# USB_Sound_Card_with_PCM2902.net
KiCad netlist of a schematic drawn in EAGLE
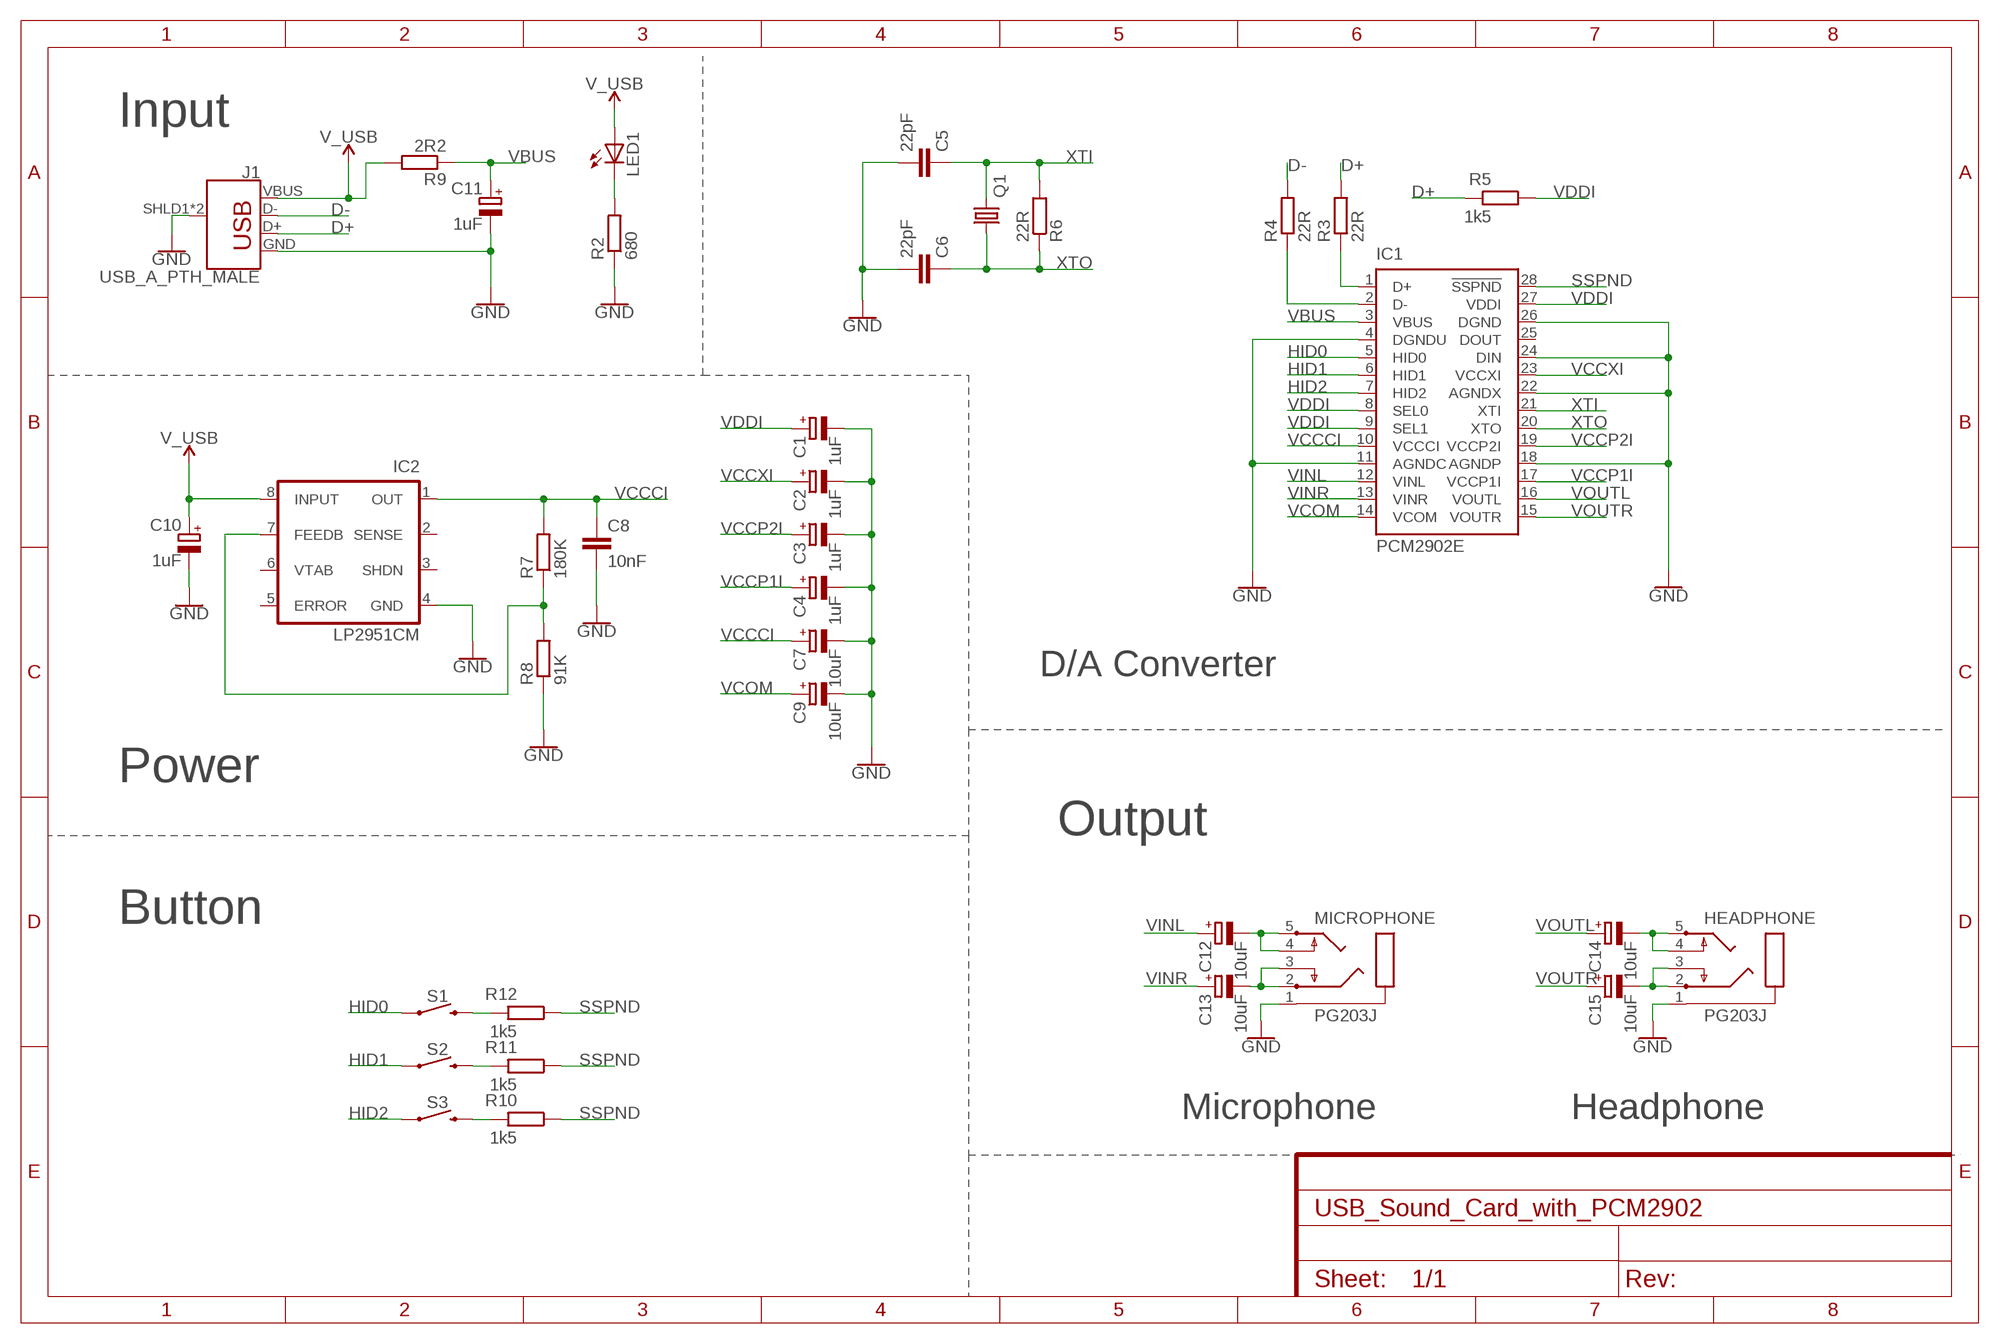
[diagram p0: schematic, sheet 1]

(export (version "E")
  (design (tool "Eeschema 10.0.6"))
  (components
    (comp (ref "C1")
      (value "1uF")
      (footprint "eagle-import:CT3528")
      (libsource (lib "eagle-import") (part "CPOL-EUCT3528"))
    )
    (comp (ref "C2")
      (value "1uF")
      (footprint "eagle-import:CT3528")
      (libsource (lib "eagle-import") (part "CPOL-EUCT3528"))
    )
    (comp (ref "C3")
      (value "1uF")
      (footprint "eagle-import:CT3528")
      (libsource (lib "eagle-import") (part "CPOL-EUCT3528"))
    )
    (comp (ref "C4")
      (value "1uF")
      (footprint "eagle-import:CT3528")
      (libsource (lib "eagle-import") (part "CPOL-EUCT3528"))
    )
    (comp (ref "C5")
      (value "22pF")
      (footprint "eagle-import:C0805")
      (libsource (lib "eagle-import") (part "C-EUC0805"))
    )
    (comp (ref "C6")
      (value "22pF")
      (footprint "eagle-import:C0805")
      (libsource (lib "eagle-import") (part "C-EUC0805"))
    )
    (comp (ref "C7")
      (value "10uF")
      (footprint "eagle-import:CT3528")
      (libsource (lib "eagle-import") (part "CPOL-EUCT3528"))
    )
    (comp (ref "C8")
      (value "10nF")
      (footprint "eagle-import:C0805")
      (libsource (lib "eagle-import") (part "C-EUC0805"))
    )
    (comp (ref "C9")
      (value "10uF")
      (footprint "eagle-import:CT3528")
      (libsource (lib "eagle-import") (part "CPOL-EUCT3528"))
    )
    (comp (ref "C10")
      (value "1uF")
      (footprint "eagle-import:CT3528")
      (libsource (lib "eagle-import") (part "CPOL-EUCT3528"))
    )
    (comp (ref "C11")
      (value "1uF")
      (footprint "eagle-import:CT3528")
      (libsource (lib "eagle-import") (part "CPOL-EUCT3528"))
    )
    (comp (ref "C12")
      (value "10uF")
      (footprint "eagle-import:CT3528")
      (libsource (lib "eagle-import") (part "CPOL-EUCT3528"))
    )
    (comp (ref "C13")
      (value "10uF")
      (footprint "eagle-import:CT3528")
      (libsource (lib "eagle-import") (part "CPOL-EUCT3528"))
    )
    (comp (ref "C14")
      (value "10uF")
      (footprint "eagle-import:CT3528")
      (libsource (lib "eagle-import") (part "CPOL-EUCT3528"))
    )
    (comp (ref "C15")
      (value "10uF")
      (footprint "eagle-import:CT3528")
      (libsource (lib "eagle-import") (part "CPOL-EUCT3528"))
    )
    (comp (ref "HEADPHONE")
      (value "PG203J")
      (footprint "eagle-import:PG203J")
      (libsource (lib "eagle-import") (part "PG203J"))
    )
    (comp (ref "IC1")
      (value "PCM2902E")
      (footprint "eagle-import:SSOP28DB")
      (libsource (lib "eagle-import") (part "PCM2902E"))
    )
    (comp (ref "IC2")
      (value "LP2951CM")
      (footprint "eagle-import:SO-08")
      (libsource (lib "eagle-import") (part "LP2951?CM"))
    )
    (comp (ref "J1")
      (value "USB_A_PTH_MALE")
      (footprint "eagle-import:USB-A-H")
      (libsource (lib "eagle-import") (part "USB_A_PTH_MALE"))
    )
    (comp (ref "LED1")
      (value "LEDCHIP-LED0805")
      (footprint "eagle-import:CHIP-LED0805")
      (libsource (lib "eagle-import") (part "LEDCHIP-LED0805"))
    )
    (comp (ref "MICROPHONE")
      (value "PG203J")
      (footprint "eagle-import:PG203J")
      (libsource (lib "eagle-import") (part "PG203J"))
    )
    (comp (ref "Q1")
      (value "CRYSTALHC49UP")
      (footprint "eagle-import:HC49UP")
      (libsource (lib "eagle-import") (part "CRYSTALHC49UP"))
    )
    (comp (ref "R2")
      (value "680")
      (footprint "eagle-import:M0805")
      (libsource (lib "eagle-import") (part "R-EU_M0805"))
    )
    (comp (ref "R3")
      (value "22R")
      (footprint "eagle-import:M0805")
      (libsource (lib "eagle-import") (part "R-EU_M0805"))
    )
    (comp (ref "R4")
      (value "22R")
      (footprint "eagle-import:M0805")
      (libsource (lib "eagle-import") (part "R-EU_M0805"))
    )
    (comp (ref "R5")
      (value "1k5")
      (footprint "eagle-import:M0805")
      (libsource (lib "eagle-import") (part "R-EU_M0805"))
    )
    (comp (ref "R6")
      (value "22R")
      (footprint "eagle-import:M0805")
      (libsource (lib "eagle-import") (part "R-EU_M0805"))
    )
    (comp (ref "R7")
      (value "180K")
      (footprint "eagle-import:M0805")
      (libsource (lib "eagle-import") (part "R-EU_M0805"))
    )
    (comp (ref "R8")
      (value "91K")
      (footprint "eagle-import:M0805")
      (libsource (lib "eagle-import") (part "R-EU_M0805"))
    )
    (comp (ref "R9")
      (value "2R2")
      (footprint "eagle-import:M0805")
      (libsource (lib "eagle-import") (part "R-EU_M0805"))
    )
    (comp (ref "R10")
      (value "1k5")
      (footprint "eagle-import:M0805")
      (libsource (lib "eagle-import") (part "R-EU_M0805"))
    )
    (comp (ref "R11")
      (value "1k5")
      (footprint "eagle-import:M0805")
      (libsource (lib "eagle-import") (part "R-EU_M0805"))
    )
    (comp (ref "R12")
      (value "1k5")
      (footprint "eagle-import:M0805")
      (libsource (lib "eagle-import") (part "R-EU_M0805"))
    )
    (comp (ref "S1")
      (value "MOMENTARY-SWITCH-SPST-PTH-6.0MM")
      (footprint "eagle-import:TACTILE_SWITCH_PTH_6.0MM")
      (libsource (lib "eagle-import") (part "MOMENTARY-SWITCH-SPST-PTH-6.0MM"))
    )
    (comp (ref "S2")
      (value "MOMENTARY-SWITCH-SPST-PTH-6.0MM")
      (footprint "eagle-import:TACTILE_SWITCH_PTH_6.0MM")
      (libsource (lib "eagle-import") (part "MOMENTARY-SWITCH-SPST-PTH-6.0MM"))
    )
    (comp (ref "S3")
      (value "MOMENTARY-SWITCH-SPST-PTH-6.0MM")
      (footprint "eagle-import:TACTILE_SWITCH_PTH_6.0MM")
      (libsource (lib "eagle-import") (part "MOMENTARY-SWITCH-SPST-PTH-6.0MM"))
    )
  )
  (nets
    (net (code "1") (name "/D+") (class "Default")
      (node (ref "J1") (pin "D+") (pinfunction "D+_D+") (pintype "bidirectional"))
      (node (ref "R3") (pin "2") (pinfunction "2_2") (pintype "passive"))
      (node (ref "R5") (pin "2") (pinfunction "2_2") (pintype "passive"))
    )
    (net (code "2") (name "/D-") (class "Default")
      (node (ref "J1") (pin "D-") (pinfunction "D-_D-") (pintype "bidirectional"))
      (node (ref "R4") (pin "2") (pinfunction "2_2") (pintype "passive"))
    )
    (net (code "3") (name "/HID0") (class "Default")
      (node (ref "IC1") (pin "5") (pinfunction "HID0_5") (pintype "input"))
      (node (ref "S1") (pin "1") (pinfunction "1_1") (pintype "passive"))
    )
    (net (code "4") (name "/HID1") (class "Default")
      (node (ref "IC1") (pin "6") (pinfunction "HID1_6") (pintype "input"))
      (node (ref "S2") (pin "1") (pinfunction "1_1") (pintype "passive"))
    )
    (net (code "5") (name "/HID2") (class "Default")
      (node (ref "IC1") (pin "7") (pinfunction "HID2_7") (pintype "input"))
      (node (ref "S3") (pin "1") (pinfunction "1_1") (pintype "passive"))
    )
    (net (code "6") (name "/SSPND") (class "Default")
      (node (ref "IC1") (pin "28") (pinfunction "~{SSPND}_28") (pintype "output"))
      (node (ref "R10") (pin "1") (pinfunction "1_1") (pintype "passive"))
      (node (ref "R11") (pin "1") (pinfunction "1_1") (pintype "passive"))
      (node (ref "R12") (pin "1") (pinfunction "1_1") (pintype "passive"))
    )
    (net (code "7") (name "/VBUS") (class "Default")
      (node (ref "C11") (pin "+") (pinfunction "+_+") (pintype "passive"))
      (node (ref "IC1") (pin "3") (pinfunction "VBUS_3") (pintype "power_in"))
      (node (ref "R9") (pin "1") (pinfunction "1_1") (pintype "passive"))
    )
    (net (code "8") (name "/VCCCI") (class "Default")
      (node (ref "C7") (pin "+") (pinfunction "+_+") (pintype "passive"))
      (node (ref "C8") (pin "1") (pinfunction "1_1") (pintype "passive"))
      (node (ref "IC1") (pin "10") (pinfunction "VCCCI_10") (pintype "power_in"))
      (node (ref "IC2") (pin "1") (pinfunction "OUT_1") (pintype "output"))
      (node (ref "R7") (pin "2") (pinfunction "2_2") (pintype "passive"))
    )
    (net (code "9") (name "/VCCP1I") (class "Default")
      (node (ref "C4") (pin "+") (pinfunction "+_+") (pintype "passive"))
      (node (ref "IC1") (pin "17") (pinfunction "VCCP1I_17") (pintype "input"))
    )
    (net (code "10") (name "/VCCP2I") (class "Default")
      (node (ref "C3") (pin "+") (pinfunction "+_+") (pintype "passive"))
      (node (ref "IC1") (pin "19") (pinfunction "VCCP2I_19") (pintype "power_in"))
    )
    (net (code "11") (name "/VCCXI") (class "Default")
      (node (ref "C2") (pin "+") (pinfunction "+_+") (pintype "passive"))
      (node (ref "IC1") (pin "23") (pinfunction "VCCXI_23") (pintype "power_in"))
    )
    (net (code "12") (name "/VCOM") (class "Default")
      (node (ref "C9") (pin "+") (pinfunction "+_+") (pintype "passive"))
      (node (ref "IC1") (pin "14") (pinfunction "VCOM_14") (pintype "power_in"))
    )
    (net (code "13") (name "/VDDI") (class "Default")
      (node (ref "C1") (pin "+") (pinfunction "+_+") (pintype "passive"))
      (node (ref "IC1") (pin "27") (pinfunction "VDDI_27") (pintype "power_in"))
      (node (ref "IC1") (pin "8") (pinfunction "SEL0_8") (pintype "input"))
      (node (ref "IC1") (pin "9") (pinfunction "SEL1_9") (pintype "input"))
      (node (ref "R5") (pin "1") (pinfunction "1_1") (pintype "passive"))
    )
    (net (code "14") (name "/VINL") (class "Default")
      (node (ref "C12") (pin "+") (pinfunction "+_+") (pintype "passive"))
      (node (ref "IC1") (pin "12") (pinfunction "VINL_12") (pintype "input"))
    )
    (net (code "15") (name "/VINR") (class "Default")
      (node (ref "C13") (pin "+") (pinfunction "+_+") (pintype "passive"))
      (node (ref "IC1") (pin "13") (pinfunction "VINR_13") (pintype "input"))
    )
    (net (code "16") (name "/VOUTL") (class "Default")
      (node (ref "C14") (pin "+") (pinfunction "+_+") (pintype "passive"))
      (node (ref "IC1") (pin "16") (pinfunction "VOUTL_16") (pintype "output"))
    )
    (net (code "17") (name "/VOUTR") (class "Default")
      (node (ref "C15") (pin "+") (pinfunction "+_+") (pintype "passive"))
      (node (ref "IC1") (pin "15") (pinfunction "VOUTR_15") (pintype "output"))
    )
    (net (code "18") (name "/XTI") (class "Default")
      (node (ref "C5") (pin "1") (pinfunction "1_1") (pintype "passive"))
      (node (ref "IC1") (pin "21") (pinfunction "XTI_21") (pintype "input"))
      (node (ref "Q1") (pin "2") (pinfunction "2_2") (pintype "passive"))
      (node (ref "R6") (pin "2") (pinfunction "2_2") (pintype "passive"))
    )
    (net (code "19") (name "/XTO") (class "Default")
      (node (ref "C6") (pin "1") (pinfunction "1_1") (pintype "passive"))
      (node (ref "IC1") (pin "20") (pinfunction "XTO_20") (pintype "output"))
      (node (ref "Q1") (pin "1") (pinfunction "1_1") (pintype "passive"))
      (node (ref "R6") (pin "1") (pinfunction "1_1") (pintype "passive"))
    )
    (net (code "20") (name "GND") (class "Default")
      (node (ref "C1") (pin "-") (pinfunction "-_-") (pintype "passive"))
      (node (ref "C10") (pin "-") (pinfunction "-_-") (pintype "passive"))
      (node (ref "C11") (pin "-") (pinfunction "-_-") (pintype "passive"))
      (node (ref "C2") (pin "-") (pinfunction "-_-") (pintype "passive"))
      (node (ref "C3") (pin "-") (pinfunction "-_-") (pintype "passive"))
      (node (ref "C4") (pin "-") (pinfunction "-_-") (pintype "passive"))
      (node (ref "C5") (pin "2") (pinfunction "2_2") (pintype "passive"))
      (node (ref "C6") (pin "2") (pinfunction "2_2") (pintype "passive"))
      (node (ref "C7") (pin "-") (pinfunction "-_-") (pintype "passive"))
      (node (ref "C8") (pin "2") (pinfunction "2_2") (pintype "passive"))
      (node (ref "C9") (pin "-") (pinfunction "-_-") (pintype "passive"))
      (node (ref "HEADPHONE") (pin "1") (pinfunction "1_1") (pintype "passive"))
      (node (ref "IC1") (pin "11") (pinfunction "AGNDC_11") (pintype "power_in"))
      (node (ref "IC1") (pin "18") (pinfunction "AGNDP_18") (pintype "power_in"))
      (node (ref "IC1") (pin "22") (pinfunction "AGNDX_22") (pintype "power_in"))
      (node (ref "IC1") (pin "24") (pinfunction "DIN_24") (pintype "input"))
      (node (ref "IC1") (pin "26") (pinfunction "DGND_26") (pintype "power_in"))
      (node (ref "IC1") (pin "4") (pinfunction "DGNDU_4") (pintype "power_in"))
      (node (ref "IC2") (pin "4") (pinfunction "GND_4") (pintype "power_in"))
      (node (ref "J1") (pin "GND") (pinfunction "GND_GND") (pintype "power_in"))
      (node (ref "J1") (pin "SHLD1") (pinfunction "SHIELD_SHLD1") (pintype "bidirectional"))
      (node (ref "J1") (pin "SHLD2") (pinfunction "SHIELD_SHLD2") (pintype "bidirectional"))
      (node (ref "MICROPHONE") (pin "1") (pinfunction "1_1") (pintype "passive"))
      (node (ref "R2") (pin "1") (pinfunction "1_1") (pintype "passive"))
      (node (ref "R8") (pin "1") (pinfunction "1_1") (pintype "passive"))
    )
    (net (code "21") (name "Net-(C12-Pad-)") (class "Default")
      (node (ref "C12") (pin "-") (pinfunction "-_-") (pintype "passive"))
      (node (ref "MICROPHONE") (pin "4") (pinfunction "4_4") (pintype "passive"))
      (node (ref "MICROPHONE") (pin "5") (pinfunction "5_5") (pintype "passive"))
    )
    (net (code "22") (name "Net-(C13-Pad-)") (class "Default")
      (node (ref "C13") (pin "-") (pinfunction "-_-") (pintype "passive"))
      (node (ref "MICROPHONE") (pin "2") (pinfunction "2_2") (pintype "passive"))
      (node (ref "MICROPHONE") (pin "3") (pinfunction "3_3") (pintype "passive"))
    )
    (net (code "23") (name "Net-(C14-Pad-)") (class "Default")
      (node (ref "C14") (pin "-") (pinfunction "-_-") (pintype "passive"))
      (node (ref "HEADPHONE") (pin "4") (pinfunction "4_4") (pintype "passive"))
      (node (ref "HEADPHONE") (pin "5") (pinfunction "5_5") (pintype "passive"))
    )
    (net (code "24") (name "Net-(C15-Pad-)") (class "Default")
      (node (ref "C15") (pin "-") (pinfunction "-_-") (pintype "passive"))
      (node (ref "HEADPHONE") (pin "2") (pinfunction "2_2") (pintype "passive"))
      (node (ref "HEADPHONE") (pin "3") (pinfunction "3_3") (pintype "passive"))
    )
    (net (code "25") (name "Net-(IC1-D+)") (class "Default")
      (node (ref "IC1") (pin "1") (pinfunction "D+_1") (pintype "bidirectional"))
      (node (ref "R3") (pin "1") (pinfunction "1_1") (pintype "passive"))
    )
    (net (code "26") (name "Net-(IC1-D-)") (class "Default")
      (node (ref "IC1") (pin "2") (pinfunction "D-_2") (pintype "bidirectional"))
      (node (ref "R4") (pin "1") (pinfunction "1_1") (pintype "passive"))
    )
    (net (code "27") (name "Net-(IC2-FEEDB)") (class "Default")
      (node (ref "IC2") (pin "7") (pinfunction "FEEDB_7") (pintype "output"))
      (node (ref "R7") (pin "1") (pinfunction "1_1") (pintype "passive"))
      (node (ref "R8") (pin "2") (pinfunction "2_2") (pintype "passive"))
    )
    (net (code "28") (name "Net-(LED1-PadC)") (class "Default")
      (node (ref "LED1") (pin "C") (pinfunction "C_C") (pintype "passive"))
      (node (ref "R2") (pin "2") (pinfunction "2_2") (pintype "passive"))
    )
    (net (code "29") (name "Net-(S1-2)") (class "Default")
      (node (ref "R12") (pin "2") (pinfunction "2_2") (pintype "passive"))
      (node (ref "S1") (pin "3") (pinfunction "2_3") (pintype "passive"))
    )
    (net (code "30") (name "Net-(S2-2)") (class "Default")
      (node (ref "R11") (pin "2") (pinfunction "2_2") (pintype "passive"))
      (node (ref "S2") (pin "3") (pinfunction "2_3") (pintype "passive"))
    )
    (net (code "31") (name "Net-(S3-2)") (class "Default")
      (node (ref "R10") (pin "2") (pinfunction "2_2") (pintype "passive"))
      (node (ref "S3") (pin "3") (pinfunction "2_3") (pintype "passive"))
    )
    (net (code "32") (name "V_USB") (class "Default")
      (node (ref "C10") (pin "+") (pinfunction "+_+") (pintype "passive"))
      (node (ref "IC2") (pin "8") (pinfunction "INPUT_8") (pintype "passive"))
      (node (ref "J1") (pin "VBUS") (pinfunction "VBUS_VBUS") (pintype "power_in"))
      (node (ref "LED1") (pin "A") (pinfunction "A_A") (pintype "passive"))
      (node (ref "R9") (pin "2") (pinfunction "2_2") (pintype "passive"))
    )
    (net (code "33") (name "unconnected-(IC1-DOUT-Pad25)") (class "Default")
      (node (ref "IC1") (pin "25") (pinfunction "DOUT_25") (pintype "output"))
    )
    (net (code "34") (name "unconnected-(IC2-ERROR-Pad5)") (class "Default")
      (node (ref "IC2") (pin "5") (pinfunction "ERROR_5") (pintype "output"))
    )
    (net (code "35") (name "unconnected-(IC2-SENSE-Pad2)") (class "Default")
      (node (ref "IC2") (pin "2") (pinfunction "SENSE_2") (pintype "input"))
    )
    (net (code "36") (name "unconnected-(IC2-SHDN-Pad3)") (class "Default")
      (node (ref "IC2") (pin "3") (pinfunction "SHDN_3") (pintype "input"))
    )
    (net (code "37") (name "unconnected-(IC2-VTAB-Pad6)") (class "Default")
      (node (ref "IC2") (pin "6") (pinfunction "VTAB_6") (pintype "input"))
    )
  )
)
